# pcb-bldc-servo-4.net
KiCad netlist of a schematic drawn in EAGLE
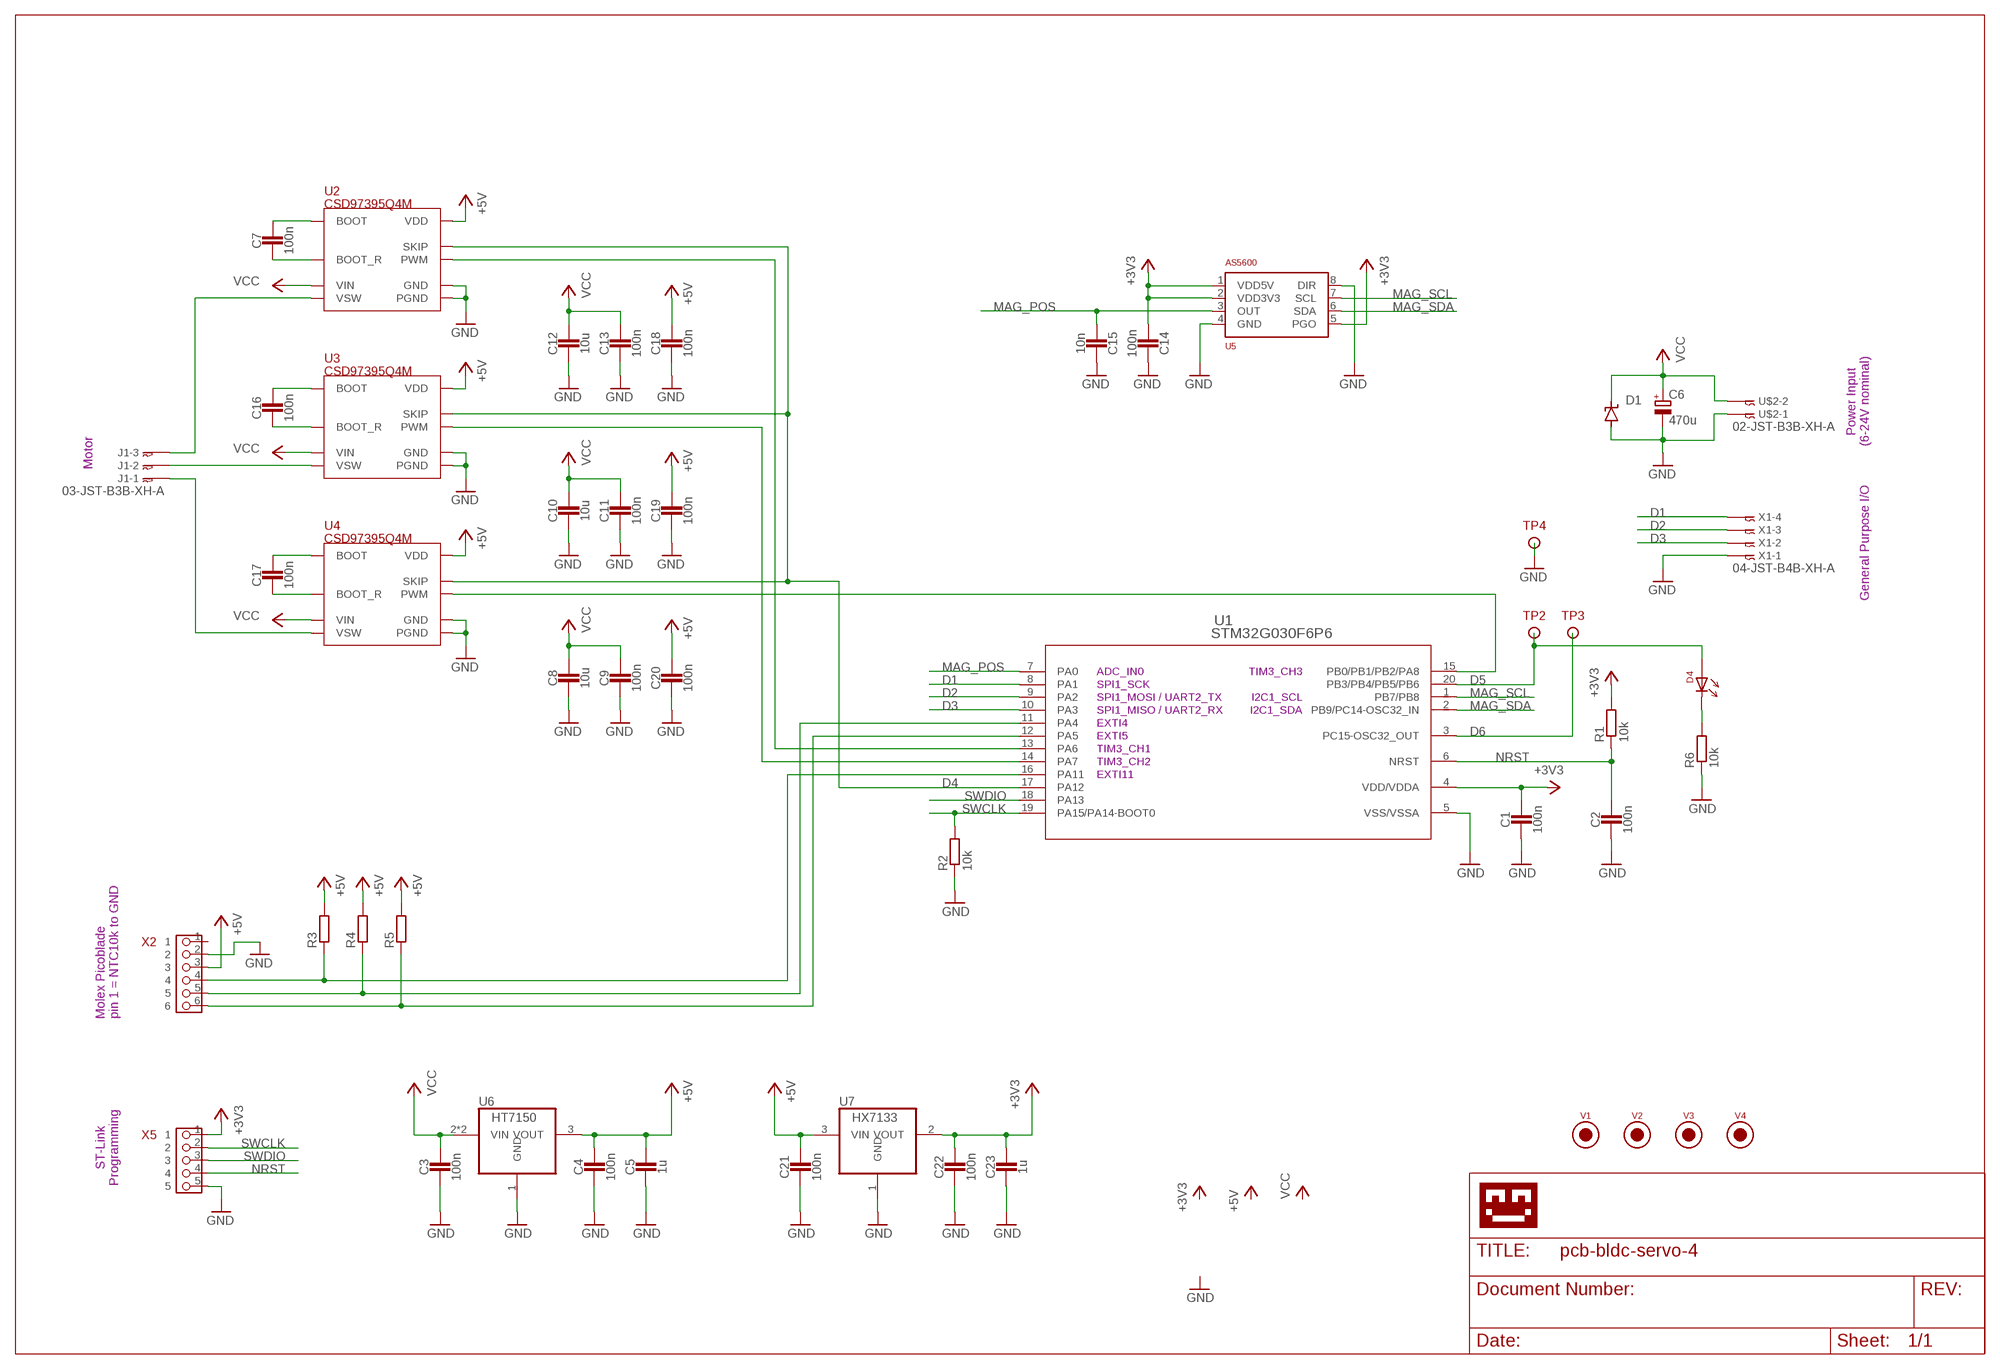
[diagram p0: schematic, sheet 1]

(export (version "E")
  (design (tool "Eeschema 10.0.6"))
  (components
    (comp (ref "C1")
      (value "100n")
      (footprint "eagle-import:0603_CAP")
      (libsource (lib "eagle-import") (part "CAPACITOR0603_CAP"))
    )
    (comp (ref "C2")
      (value "100n")
      (footprint "eagle-import:0603_CAP")
      (libsource (lib "eagle-import") (part "CAPACITOR0603_CAP"))
    )
    (comp (ref "C3")
      (value "100n")
      (footprint "eagle-import:0603_CAP")
      (libsource (lib "eagle-import") (part "CAPACITOR0603_CAP"))
    )
    (comp (ref "C4")
      (value "100n")
      (footprint "eagle-import:0603_CAP")
      (libsource (lib "eagle-import") (part "CAPACITOR0603_CAP"))
    )
    (comp (ref "C5")
      (value "1u")
      (footprint "eagle-import:0603_CAP")
      (libsource (lib "eagle-import") (part "CAPACITOR0603_CAP"))
    )
    (comp (ref "C6")
      (value "470u")
      (footprint "eagle-import:153CLV-1010")
      (libsource (lib "eagle-import") (part "CPOL-EU153CLV-1010"))
    )
    (comp (ref "C7")
      (value "100n")
      (footprint "eagle-import:0603_CAP")
      (libsource (lib "eagle-import") (part "CAPACITOR0603_CAP"))
    )
    (comp (ref "C8")
      (value "10u")
      (footprint "eagle-import:1206_CAP")
      (libsource (lib "eagle-import") (part "CAPACITOR1206_CAP"))
    )
    (comp (ref "C9")
      (value "100n")
      (footprint "eagle-import:0603_CAP")
      (libsource (lib "eagle-import") (part "CAPACITOR0603_CAP"))
    )
    (comp (ref "C10")
      (value "10u")
      (footprint "eagle-import:1206_CAP")
      (libsource (lib "eagle-import") (part "CAPACITOR1206_CAP"))
    )
    (comp (ref "C11")
      (value "100n")
      (footprint "eagle-import:0603_CAP")
      (libsource (lib "eagle-import") (part "CAPACITOR0603_CAP"))
    )
    (comp (ref "C12")
      (value "10u")
      (footprint "eagle-import:1206_CAP")
      (libsource (lib "eagle-import") (part "CAPACITOR1206_CAP"))
    )
    (comp (ref "C13")
      (value "100n")
      (footprint "eagle-import:0603_CAP")
      (libsource (lib "eagle-import") (part "CAPACITOR0603_CAP"))
    )
    (comp (ref "C14")
      (value "100n")
      (footprint "eagle-import:0603_CAP")
      (libsource (lib "eagle-import") (part "CAPACITOR0603_CAP"))
    )
    (comp (ref "C15")
      (value "10n")
      (footprint "eagle-import:0603_CAP")
      (libsource (lib "eagle-import") (part "CAPACITOR0603_CAP"))
    )
    (comp (ref "C16")
      (value "100n")
      (footprint "eagle-import:0603_CAP")
      (libsource (lib "eagle-import") (part "CAPACITOR0603_CAP"))
    )
    (comp (ref "C17")
      (value "100n")
      (footprint "eagle-import:0603_CAP")
      (libsource (lib "eagle-import") (part "CAPACITOR0603_CAP"))
    )
    (comp (ref "C18")
      (value "100n")
      (footprint "eagle-import:0603_CAP")
      (libsource (lib "eagle-import") (part "CAPACITOR0603_CAP"))
    )
    (comp (ref "C19")
      (value "100n")
      (footprint "eagle-import:0603_CAP")
      (libsource (lib "eagle-import") (part "CAPACITOR0603_CAP"))
    )
    (comp (ref "C20")
      (value "100n")
      (footprint "eagle-import:0603_CAP")
      (libsource (lib "eagle-import") (part "CAPACITOR0603_CAP"))
    )
    (comp (ref "C21")
      (value "100n")
      (footprint "eagle-import:0603_CAP")
      (libsource (lib "eagle-import") (part "CAPACITOR0603_CAP"))
    )
    (comp (ref "C22")
      (value "100n")
      (footprint "eagle-import:0603_CAP")
      (libsource (lib "eagle-import") (part "CAPACITOR0603_CAP"))
    )
    (comp (ref "C23")
      (value "1u")
      (footprint "eagle-import:0603_CAP")
      (libsource (lib "eagle-import") (part "CAPACITOR0603_CAP"))
    )
    (comp (ref "D1")
      (value "SUPPRESSOR-SMBJ")
      (footprint "eagle-import:SMBJ")
      (libsource (lib "eagle-import") (part "SUPPRESSOR-SMBJ"))
    )
    (comp (ref "D4")
      (value "LED-0805")
      (footprint "eagle-import:0805-DOT")
      (libsource (lib "eagle-import") (part "LED-0805"))
    )
    (comp (ref "J1")
      (value "03-JST-B3B-XH-A")
      (footprint "eagle-import:B3B-XH")
      (libsource (lib "eagle-import") (part "03-JST-B3B-XH-A"))
    )
    (comp (ref "R1")
      (value "10k")
      (footprint "eagle-import:0603-RES")
      (libsource (lib "eagle-import") (part "RESISTOR0603_RES"))
    )
    (comp (ref "R2")
      (value "10k")
      (footprint "eagle-import:0603-RES")
      (libsource (lib "eagle-import") (part "RESISTOR0603_RES"))
    )
    (comp (ref "R3")
      (value "RESISTOR0603_RES")
      (footprint "eagle-import:0603-RES")
      (libsource (lib "eagle-import") (part "RESISTOR0603_RES"))
    )
    (comp (ref "R4")
      (value "RESISTOR0603_RES")
      (footprint "eagle-import:0603-RES")
      (libsource (lib "eagle-import") (part "RESISTOR0603_RES"))
    )
    (comp (ref "R5")
      (value "RESISTOR0603_RES")
      (footprint "eagle-import:0603-RES")
      (libsource (lib "eagle-import") (part "RESISTOR0603_RES"))
    )
    (comp (ref "R6")
      (value "10k")
      (footprint "eagle-import:0603-RES")
      (libsource (lib "eagle-import") (part "RESISTOR0603_RES"))
    )
    (comp (ref "TP2")
      (value "TESTPIN1MM")
      (footprint "eagle-import:PIN-SMD-1X1-TEST_1M0")
      (libsource (lib "eagle-import") (part "TESTPIN1MM"))
    )
    (comp (ref "TP3")
      (value "TESTPIN1MM")
      (footprint "eagle-import:PIN-SMD-1X1-TEST_1M0")
      (libsource (lib "eagle-import") (part "TESTPIN1MM"))
    )
    (comp (ref "TP4")
      (value "TESTPIN1MM")
      (footprint "eagle-import:PIN-SMD-1X1-TEST_1M0")
      (libsource (lib "eagle-import") (part "TESTPIN1MM"))
    )
    (comp (ref "U$1")
      (value "LOGO-TOBENG-1MM-FINISH")
      (footprint "eagle-import:TOBENG-1MM-FINISH")
      (libsource (lib "eagle-import") (part "LOGO-TOBENG-1MM-FINISH"))
    )
    (comp (ref "U$2")
      (value "02-JST-B3B-XH-A")
      (footprint "eagle-import:B2B-XH")
      (libsource (lib "eagle-import") (part "02-JST-B3B-XH-A"))
    )
    (comp (ref "U1")
      (value "STM32G030F6P6")
      (footprint "eagle-import:TSSOP20")
      (fields (field (name "COPYRIGHT") "Copyright (C) 2024 Ultra Librarian. All rights reserved."))
      (libsource (lib "eagle-import") (part "STM32G030F6P6"))
    )
    (comp (ref "U2")
      (value "CSD97395Q4M")
      (footprint "eagle-import:CSD97395Q4M")
      (libsource (lib "eagle-import") (part "CSD97395Q4M"))
    )
    (comp (ref "U3")
      (value "CSD97395Q4M")
      (footprint "eagle-import:CSD97395Q4M")
      (libsource (lib "eagle-import") (part "CSD97395Q4M"))
    )
    (comp (ref "U4")
      (value "CSD97395Q4M")
      (footprint "eagle-import:CSD97395Q4M")
      (libsource (lib "eagle-import") (part "CSD97395Q4M"))
    )
    (comp (ref "U5")
      (value "AS5600")
      (footprint "eagle-import:SOIC-8")
      (libsource (lib "eagle-import") (part "AS5600"))
    )
    (comp (ref "U6")
      (value "HT7150")
      (footprint "eagle-import:SOT-89")
      (libsource (lib "eagle-import") (part "LDO-HT71XX"))
    )
    (comp (ref "U7")
      (value "HX7133")
      (footprint "eagle-import:SOT-23")
      (libsource (lib "eagle-import") (part "LDO-23"))
    )
    (comp (ref "V1")
      (value "FIDUCIAL2MM")
      (footprint "eagle-import:FIDUCIAL_2MM")
      (libsource (lib "eagle-import") (part "FIDUCIAL2MM"))
    )
    (comp (ref "V2")
      (value "FIDUCIAL2MM")
      (footprint "eagle-import:FIDUCIAL_2MM")
      (libsource (lib "eagle-import") (part "FIDUCIAL2MM"))
    )
    (comp (ref "V3")
      (value "FIDUCIAL2MM")
      (footprint "eagle-import:FIDUCIAL_2MM")
      (libsource (lib "eagle-import") (part "FIDUCIAL2MM"))
    )
    (comp (ref "V4")
      (value "FIDUCIAL2MM")
      (footprint "eagle-import:FIDUCIAL_2MM")
      (libsource (lib "eagle-import") (part "FIDUCIAL2MM"))
    )
    (comp (ref "X1")
      (value "04-JST-B4B-XH-A")
      (footprint "eagle-import:B4B-XH")
      (libsource (lib "eagle-import") (part "04-JST-B4B-XH-A"))
    )
    (comp (ref "X2")
      (value "PIN_6X1")
      (footprint "eagle-import:PIN_6X1_MOLEX_PICOBLADE")
      (libsource (lib "eagle-import") (part "PIN_6X1"))
    )
    (comp (ref "X5")
      (value "PIN_5X1HD")
      (footprint "eagle-import:PIN_5X1_HD")
      (libsource (lib "eagle-import") (part "PIN_5X1HD"))
    )
  )
  (nets
    (net (code "1") (name "+3V3") (class "Default")
      (node (ref "C1") (pin "1") (pinfunction "1_1") (pintype "bidirectional"))
      (node (ref "C14") (pin "1") (pinfunction "1_1") (pintype "bidirectional"))
      (node (ref "C22") (pin "1") (pinfunction "1_1") (pintype "bidirectional"))
      (node (ref "C23") (pin "1") (pinfunction "1_1") (pintype "bidirectional"))
      (node (ref "R1") (pin "2") (pinfunction "2_2") (pintype "passive"))
      (node (ref "U1") (pin "4") (pinfunction "VDD/VDDA_4") (pintype "power_in"))
      (node (ref "U5") (pin "1") (pinfunction "VDD5V_1") (pintype "bidirectional"))
      (node (ref "U5") (pin "2") (pinfunction "VDD3V3_2") (pintype "bidirectional"))
      (node (ref "U5") (pin "5") (pinfunction "PGO_5") (pintype "bidirectional"))
      (node (ref "U7") (pin "2") (pinfunction "VOUT_2") (pintype "output"))
      (node (ref "X5") (pin "1") (pinfunction "1_1") (pintype "bidirectional"))
    )
    (net (code "2") (name "+5V") (class "Default")
      (node (ref "C18") (pin "1") (pinfunction "1_1") (pintype "bidirectional"))
      (node (ref "C19") (pin "1") (pinfunction "1_1") (pintype "bidirectional"))
      (node (ref "C20") (pin "1") (pinfunction "1_1") (pintype "bidirectional"))
      (node (ref "C21") (pin "1") (pinfunction "1_1") (pintype "bidirectional"))
      (node (ref "C4") (pin "1") (pinfunction "1_1") (pintype "bidirectional"))
      (node (ref "C5") (pin "1") (pinfunction "1_1") (pintype "bidirectional"))
      (node (ref "R3") (pin "2") (pinfunction "2_2") (pintype "passive"))
      (node (ref "R4") (pin "2") (pinfunction "2_2") (pintype "passive"))
      (node (ref "R5") (pin "2") (pinfunction "2_2") (pintype "passive"))
      (node (ref "U2") (pin "VDD") (pinfunction "VDD_VDD") (pintype "bidirectional"))
      (node (ref "U2") (pin "VDD1") (pinfunction "VDD_VDD1") (pintype "bidirectional"))
      (node (ref "U3") (pin "VDD") (pinfunction "VDD_VDD") (pintype "bidirectional"))
      (node (ref "U3") (pin "VDD1") (pinfunction "VDD_VDD1") (pintype "bidirectional"))
      (node (ref "U4") (pin "VDD") (pinfunction "VDD_VDD") (pintype "bidirectional"))
      (node (ref "U4") (pin "VDD1") (pinfunction "VDD_VDD1") (pintype "bidirectional"))
      (node (ref "U6") (pin "3") (pinfunction "VOUT_3") (pintype "output"))
      (node (ref "U7") (pin "3") (pinfunction "VIN_3") (pintype "input"))
      (node (ref "X2") (pin "3") (pinfunction "3_3") (pintype "bidirectional"))
    )
    (net (code "3") (name "/D1") (class "Default")
      (node (ref "U1") (pin "8") (pinfunction "PA1_8") (pintype "bidirectional"))
      (node (ref "X1") (pin "P$4") (pinfunction "1_P$4") (pintype "passive"))
    )
    (net (code "4") (name "/D2") (class "Default")
      (node (ref "U1") (pin "9") (pinfunction "PA2_9") (pintype "bidirectional"))
      (node (ref "X1") (pin "P$3") (pinfunction "1_P$3") (pintype "passive"))
    )
    (net (code "5") (name "/D3") (class "Default")
      (node (ref "U1") (pin "10") (pinfunction "PA3_10") (pintype "bidirectional"))
      (node (ref "X1") (pin "P$2") (pinfunction "1_P$2") (pintype "passive"))
    )
    (net (code "6") (name "/D4") (class "Default")
      (node (ref "U1") (pin "17") (pinfunction "PA12_17") (pintype "bidirectional"))
      (node (ref "U2") (pin "SKIP") (pinfunction "SKIP_SKIP") (pintype "bidirectional"))
      (node (ref "U2") (pin "SKIP1") (pinfunction "SKIP_SKIP1") (pintype "bidirectional"))
      (node (ref "U3") (pin "SKIP") (pinfunction "SKIP_SKIP") (pintype "bidirectional"))
      (node (ref "U3") (pin "SKIP1") (pinfunction "SKIP_SKIP1") (pintype "bidirectional"))
      (node (ref "U4") (pin "SKIP") (pinfunction "SKIP_SKIP") (pintype "bidirectional"))
      (node (ref "U4") (pin "SKIP1") (pinfunction "SKIP_SKIP1") (pintype "bidirectional"))
    )
    (net (code "7") (name "/D5") (class "Default")
      (node (ref "D4") (pin "1") (pinfunction "1_1") (pintype "bidirectional"))
      (node (ref "TP2") (pin "1") (pinfunction "1_1") (pintype "bidirectional"))
      (node (ref "U1") (pin "20") (pinfunction "PB3/PB4/PB5/PB6_20") (pintype "bidirectional"))
    )
    (net (code "8") (name "/D6") (class "Default")
      (node (ref "TP3") (pin "1") (pinfunction "1_1") (pintype "bidirectional"))
      (node (ref "U1") (pin "3") (pinfunction "PC15-OSC32_OUT_3") (pintype "bidirectional"))
    )
    (net (code "9") (name "/MAG_POS") (class "Default")
      (node (ref "C15") (pin "1") (pinfunction "1_1") (pintype "bidirectional"))
      (node (ref "U1") (pin "7") (pinfunction "PA0_7") (pintype "bidirectional"))
      (node (ref "U5") (pin "3") (pinfunction "OUT_3") (pintype "bidirectional"))
    )
    (net (code "10") (name "/MAG_SCL") (class "Default")
      (node (ref "U1") (pin "1") (pinfunction "PB7/PB8_1") (pintype "bidirectional"))
      (node (ref "U5") (pin "7") (pinfunction "SCL_7") (pintype "bidirectional"))
    )
    (net (code "11") (name "/MAG_SDA") (class "Default")
      (node (ref "U1") (pin "2") (pinfunction "PB9/PC14-OSC32_IN_2") (pintype "bidirectional"))
      (node (ref "U5") (pin "6") (pinfunction "SDA_6") (pintype "bidirectional"))
    )
    (net (code "12") (name "/NRST") (class "Default")
      (node (ref "C2") (pin "1") (pinfunction "1_1") (pintype "bidirectional"))
      (node (ref "R1") (pin "1") (pinfunction "1_1") (pintype "passive"))
      (node (ref "U1") (pin "6") (pinfunction "NRST_6") (pintype "bidirectional"))
      (node (ref "X5") (pin "4") (pinfunction "4_4") (pintype "bidirectional"))
    )
    (net (code "13") (name "/SWCLK") (class "Default")
      (node (ref "R2") (pin "2") (pinfunction "2_2") (pintype "passive"))
      (node (ref "U1") (pin "19") (pinfunction "PA15/PA14-BOOT0_19") (pintype "bidirectional"))
      (node (ref "X5") (pin "2") (pinfunction "2_2") (pintype "bidirectional"))
    )
    (net (code "14") (name "/SWDIO") (class "Default")
      (node (ref "U1") (pin "18") (pinfunction "PA13_18") (pintype "bidirectional"))
      (node (ref "X5") (pin "3") (pinfunction "3_3") (pintype "bidirectional"))
    )
    (net (code "15") (name "GND") (class "Default")
      (node (ref "C1") (pin "2") (pinfunction "2_2") (pintype "bidirectional"))
      (node (ref "C10") (pin "2") (pinfunction "2_2") (pintype "bidirectional"))
      (node (ref "C11") (pin "2") (pinfunction "2_2") (pintype "bidirectional"))
      (node (ref "C12") (pin "2") (pinfunction "2_2") (pintype "bidirectional"))
      (node (ref "C13") (pin "2") (pinfunction "2_2") (pintype "bidirectional"))
      (node (ref "C14") (pin "2") (pinfunction "2_2") (pintype "bidirectional"))
      (node (ref "C15") (pin "2") (pinfunction "2_2") (pintype "bidirectional"))
      (node (ref "C18") (pin "2") (pinfunction "2_2") (pintype "bidirectional"))
      (node (ref "C19") (pin "2") (pinfunction "2_2") (pintype "bidirectional"))
      (node (ref "C2") (pin "2") (pinfunction "2_2") (pintype "bidirectional"))
      (node (ref "C20") (pin "2") (pinfunction "2_2") (pintype "bidirectional"))
      (node (ref "C21") (pin "2") (pinfunction "2_2") (pintype "bidirectional"))
      (node (ref "C22") (pin "2") (pinfunction "2_2") (pintype "bidirectional"))
      (node (ref "C23") (pin "2") (pinfunction "2_2") (pintype "bidirectional"))
      (node (ref "C3") (pin "2") (pinfunction "2_2") (pintype "bidirectional"))
      (node (ref "C4") (pin "2") (pinfunction "2_2") (pintype "bidirectional"))
      (node (ref "C5") (pin "2") (pinfunction "2_2") (pintype "bidirectional"))
      (node (ref "C6") (pin "-") (pinfunction "-_-") (pintype "passive"))
      (node (ref "C8") (pin "2") (pinfunction "2_2") (pintype "bidirectional"))
      (node (ref "C9") (pin "2") (pinfunction "2_2") (pintype "bidirectional"))
      (node (ref "D1") (pin "A") (pinfunction "A_A") (pintype "passive"))
      (node (ref "R2") (pin "1") (pinfunction "1_1") (pintype "passive"))
      (node (ref "R6") (pin "1") (pinfunction "1_1") (pintype "passive"))
      (node (ref "TP4") (pin "1") (pinfunction "1_1") (pintype "bidirectional"))
      (node (ref "U$2") (pin "P$1") (pinfunction "1_P$1") (pintype "passive"))
      (node (ref "U1") (pin "5") (pinfunction "VSS/VSSA_5") (pintype "power_in"))
      (node (ref "U2") (pin "GND") (pinfunction "GND_GND") (pintype "bidirectional"))
      (node (ref "U2") (pin "GND1") (pinfunction "GND_GND1") (pintype "bidirectional"))
      (node (ref "U2") (pin "PGND") (pinfunction "PGND_PGND") (pintype "bidirectional"))
      (node (ref "U3") (pin "GND") (pinfunction "GND_GND") (pintype "bidirectional"))
      (node (ref "U3") (pin "GND1") (pinfunction "GND_GND1") (pintype "bidirectional"))
      (node (ref "U3") (pin "PGND") (pinfunction "PGND_PGND") (pintype "bidirectional"))
      (node (ref "U4") (pin "GND") (pinfunction "GND_GND") (pintype "bidirectional"))
      (node (ref "U4") (pin "GND1") (pinfunction "GND_GND1") (pintype "bidirectional"))
      (node (ref "U4") (pin "PGND") (pinfunction "PGND_PGND") (pintype "bidirectional"))
      (node (ref "U5") (pin "4") (pinfunction "GND_4") (pintype "bidirectional"))
      (node (ref "U5") (pin "8") (pinfunction "DIR_8") (pintype "bidirectional"))
      (node (ref "U6") (pin "1") (pinfunction "GND_1") (pintype "power_in"))
      (node (ref "U7") (pin "1") (pinfunction "GND_1") (pintype "power_in"))
      (node (ref "X1") (pin "P$1") (pinfunction "1_P$1") (pintype "passive"))
      (node (ref "X2") (pin "2") (pinfunction "2_2") (pintype "bidirectional"))
      (node (ref "X5") (pin "5") (pinfunction "5_5") (pintype "bidirectional"))
    )
    (net (code "16") (name "Net-(C7-Pad1)") (class "Default")
      (node (ref "C7") (pin "1") (pinfunction "1_1") (pintype "bidirectional"))
      (node (ref "U2") (pin "BOOT") (pinfunction "BOOT_BOOT") (pintype "bidirectional"))
      (node (ref "U2") (pin "BOOT1") (pinfunction "BOOT_BOOT1") (pintype "bidirectional"))
    )
    (net (code "17") (name "Net-(C7-Pad2)") (class "Default")
      (node (ref "C7") (pin "2") (pinfunction "2_2") (pintype "bidirectional"))
      (node (ref "U2") (pin "BOOT_R") (pinfunction "BOOT_R_BOOT_R") (pintype "bidirectional"))
      (node (ref "U2") (pin "BOOT_R1") (pinfunction "BOOT_R_BOOT_R1") (pintype "bidirectional"))
    )
    (net (code "18") (name "Net-(C16-Pad1)") (class "Default")
      (node (ref "C16") (pin "1") (pinfunction "1_1") (pintype "bidirectional"))
      (node (ref "U3") (pin "BOOT") (pinfunction "BOOT_BOOT") (pintype "bidirectional"))
      (node (ref "U3") (pin "BOOT1") (pinfunction "BOOT_BOOT1") (pintype "bidirectional"))
    )
    (net (code "19") (name "Net-(C16-Pad2)") (class "Default")
      (node (ref "C16") (pin "2") (pinfunction "2_2") (pintype "bidirectional"))
      (node (ref "U3") (pin "BOOT_R") (pinfunction "BOOT_R_BOOT_R") (pintype "bidirectional"))
      (node (ref "U3") (pin "BOOT_R1") (pinfunction "BOOT_R_BOOT_R1") (pintype "bidirectional"))
    )
    (net (code "20") (name "Net-(C17-Pad1)") (class "Default")
      (node (ref "C17") (pin "1") (pinfunction "1_1") (pintype "bidirectional"))
      (node (ref "U4") (pin "BOOT") (pinfunction "BOOT_BOOT") (pintype "bidirectional"))
      (node (ref "U4") (pin "BOOT1") (pinfunction "BOOT_BOOT1") (pintype "bidirectional"))
    )
    (net (code "21") (name "Net-(C17-Pad2)") (class "Default")
      (node (ref "C17") (pin "2") (pinfunction "2_2") (pintype "bidirectional"))
      (node (ref "U4") (pin "BOOT_R") (pinfunction "BOOT_R_BOOT_R") (pintype "bidirectional"))
      (node (ref "U4") (pin "BOOT_R1") (pinfunction "BOOT_R_BOOT_R1") (pintype "bidirectional"))
    )
    (net (code "22") (name "Net-(D4-Pad2)") (class "Default")
      (node (ref "D4") (pin "2") (pinfunction "2_2") (pintype "bidirectional"))
      (node (ref "R6") (pin "2") (pinfunction "2_2") (pintype "passive"))
    )
    (net (code "23") (name "Net-(J1A-1)") (class "Default")
      (node (ref "J1") (pin "P$1") (pinfunction "1_P$1") (pintype "passive"))
      (node (ref "U4") (pin "VSW") (pinfunction "VSW_VSW") (pintype "bidirectional"))
      (node (ref "U4") (pin "VSW1") (pinfunction "VSW_VSW1") (pintype "bidirectional"))
      (node (ref "U4") (pin "VSW2") (pinfunction "VSW_VSW2") (pintype "bidirectional"))
      (node (ref "U4") (pin "VSW3") (pinfunction "VSW_VSW3") (pintype "bidirectional"))
      (node (ref "U4") (pin "VSW4") (pinfunction "VSW_VSW4") (pintype "bidirectional"))
      (node (ref "U4") (pin "VSW5") (pinfunction "VSW_VSW5") (pintype "bidirectional"))
      (node (ref "U4") (pin "VSW6") (pinfunction "VSW_VSW6") (pintype "bidirectional"))
    )
    (net (code "24") (name "Net-(J1B-1)") (class "Default")
      (node (ref "J1") (pin "P$2") (pinfunction "1_P$2") (pintype "passive"))
      (node (ref "U3") (pin "VSW") (pinfunction "VSW_VSW") (pintype "bidirectional"))
      (node (ref "U3") (pin "VSW1") (pinfunction "VSW_VSW1") (pintype "bidirectional"))
      (node (ref "U3") (pin "VSW2") (pinfunction "VSW_VSW2") (pintype "bidirectional"))
      (node (ref "U3") (pin "VSW3") (pinfunction "VSW_VSW3") (pintype "bidirectional"))
      (node (ref "U3") (pin "VSW4") (pinfunction "VSW_VSW4") (pintype "bidirectional"))
      (node (ref "U3") (pin "VSW5") (pinfunction "VSW_VSW5") (pintype "bidirectional"))
      (node (ref "U3") (pin "VSW6") (pinfunction "VSW_VSW6") (pintype "bidirectional"))
    )
    (net (code "25") (name "Net-(J1C-1)") (class "Default")
      (node (ref "J1") (pin "P$3") (pinfunction "1_P$3") (pintype "passive"))
      (node (ref "U2") (pin "VSW") (pinfunction "VSW_VSW") (pintype "bidirectional"))
      (node (ref "U2") (pin "VSW1") (pinfunction "VSW_VSW1") (pintype "bidirectional"))
      (node (ref "U2") (pin "VSW2") (pinfunction "VSW_VSW2") (pintype "bidirectional"))
      (node (ref "U2") (pin "VSW3") (pinfunction "VSW_VSW3") (pintype "bidirectional"))
      (node (ref "U2") (pin "VSW4") (pinfunction "VSW_VSW4") (pintype "bidirectional"))
      (node (ref "U2") (pin "VSW5") (pinfunction "VSW_VSW5") (pintype "bidirectional"))
      (node (ref "U2") (pin "VSW6") (pinfunction "VSW_VSW6") (pintype "bidirectional"))
    )
    (net (code "26") (name "Net-(U1-PA4)") (class "Default")
      (node (ref "R4") (pin "1") (pinfunction "1_1") (pintype "passive"))
      (node (ref "U1") (pin "11") (pinfunction "PA4_11") (pintype "bidirectional"))
      (node (ref "X2") (pin "5") (pinfunction "5_5") (pintype "bidirectional"))
    )
    (net (code "27") (name "Net-(U1-PA5)") (class "Default")
      (node (ref "R5") (pin "1") (pinfunction "1_1") (pintype "passive"))
      (node (ref "U1") (pin "12") (pinfunction "PA5_12") (pintype "bidirectional"))
      (node (ref "X2") (pin "6") (pinfunction "6_6") (pintype "bidirectional"))
    )
    (net (code "28") (name "Net-(U1-PA6)") (class "Default")
      (node (ref "U1") (pin "13") (pinfunction "PA6_13") (pintype "bidirectional"))
      (node (ref "U2") (pin "PWM") (pinfunction "PWM_PWM") (pintype "bidirectional"))
      (node (ref "U2") (pin "PWM1") (pinfunction "PWM_PWM1") (pintype "bidirectional"))
    )
    (net (code "29") (name "Net-(U1-PA7)") (class "Default")
      (node (ref "U1") (pin "14") (pinfunction "PA7_14") (pintype "bidirectional"))
      (node (ref "U3") (pin "PWM") (pinfunction "PWM_PWM") (pintype "bidirectional"))
      (node (ref "U3") (pin "PWM1") (pinfunction "PWM_PWM1") (pintype "bidirectional"))
    )
    (net (code "30") (name "Net-(U1-PA11)") (class "Default")
      (node (ref "R3") (pin "1") (pinfunction "1_1") (pintype "passive"))
      (node (ref "U1") (pin "16") (pinfunction "PA11_16") (pintype "bidirectional"))
      (node (ref "X2") (pin "4") (pinfunction "4_4") (pintype "bidirectional"))
    )
    (net (code "31") (name "Net-(U1-PB0{slash}PB1{slash}PB2{slash}PA8)") (class "Default")
      (node (ref "U1") (pin "15") (pinfunction "PB0/PB1/PB2/PA8_15") (pintype "bidirectional"))
      (node (ref "U4") (pin "PWM") (pinfunction "PWM_PWM") (pintype "bidirectional"))
      (node (ref "U4") (pin "PWM1") (pinfunction "PWM_PWM1") (pintype "bidirectional"))
    )
    (net (code "32") (name "VCC") (class "Default")
      (node (ref "C10") (pin "1") (pinfunction "1_1") (pintype "bidirectional"))
      (node (ref "C11") (pin "1") (pinfunction "1_1") (pintype "bidirectional"))
      (node (ref "C12") (pin "1") (pinfunction "1_1") (pintype "bidirectional"))
      (node (ref "C13") (pin "1") (pinfunction "1_1") (pintype "bidirectional"))
      (node (ref "C3") (pin "1") (pinfunction "1_1") (pintype "bidirectional"))
      (node (ref "C6") (pin "+") (pinfunction "+_+") (pintype "passive"))
      (node (ref "C8") (pin "1") (pinfunction "1_1") (pintype "bidirectional"))
      (node (ref "C9") (pin "1") (pinfunction "1_1") (pintype "bidirectional"))
      (node (ref "D1") (pin "C") (pinfunction "C_C") (pintype "passive"))
      (node (ref "U$2") (pin "P$2") (pinfunction "1_P$2") (pintype "passive"))
      (node (ref "U2") (pin "VIN") (pinfunction "VIN_VIN") (pintype "bidirectional"))
      (node (ref "U2") (pin "VIN1") (pinfunction "VIN_VIN1") (pintype "bidirectional"))
      (node (ref "U2") (pin "VIN2") (pinfunction "VIN_VIN2") (pintype "bidirectional"))
      (node (ref "U2") (pin "VIN3") (pinfunction "VIN_VIN3") (pintype "bidirectional"))
      (node (ref "U2") (pin "VIN4") (pinfunction "VIN_VIN4") (pintype "bidirectional"))
      (node (ref "U2") (pin "VIN5") (pinfunction "VIN_VIN5") (pintype "bidirectional"))
      (node (ref "U2") (pin "VIN6") (pinfunction "VIN_VIN6") (pintype "bidirectional"))
      (node (ref "U3") (pin "VIN") (pinfunction "VIN_VIN") (pintype "bidirectional"))
      (node (ref "U3") (pin "VIN1") (pinfunction "VIN_VIN1") (pintype "bidirectional"))
      (node (ref "U3") (pin "VIN2") (pinfunction "VIN_VIN2") (pintype "bidirectional"))
      (node (ref "U3") (pin "VIN3") (pinfunction "VIN_VIN3") (pintype "bidirectional"))
      (node (ref "U3") (pin "VIN4") (pinfunction "VIN_VIN4") (pintype "bidirectional"))
      (node (ref "U3") (pin "VIN5") (pinfunction "VIN_VIN5") (pintype "bidirectional"))
      (node (ref "U3") (pin "VIN6") (pinfunction "VIN_VIN6") (pintype "bidirectional"))
      (node (ref "U4") (pin "VIN") (pinfunction "VIN_VIN") (pintype "bidirectional"))
      (node (ref "U4") (pin "VIN1") (pinfunction "VIN_VIN1") (pintype "bidirectional"))
      (node (ref "U4") (pin "VIN2") (pinfunction "VIN_VIN2") (pintype "bidirectional"))
      (node (ref "U4") (pin "VIN3") (pinfunction "VIN_VIN3") (pintype "bidirectional"))
      (node (ref "U4") (pin "VIN4") (pinfunction "VIN_VIN4") (pintype "bidirectional"))
      (node (ref "U4") (pin "VIN5") (pinfunction "VIN_VIN5") (pintype "bidirectional"))
      (node (ref "U4") (pin "VIN6") (pinfunction "VIN_VIN6") (pintype "bidirectional"))
      (node (ref "U6") (pin "2") (pinfunction "VIN_2") (pintype "input"))
      (node (ref "U6") (pin "2@1") (pinfunction "VIN_2@1") (pintype "input"))
    )
    (net (code "33") (name "unconnected-(X2-Pad1)") (class "Default")
      (node (ref "X2") (pin "1") (pinfunction "1_1") (pintype "bidirectional"))
    )
  )
)
